# SCNano-Main.net
KiCad netlist of a schematic drawn in Altium Designer
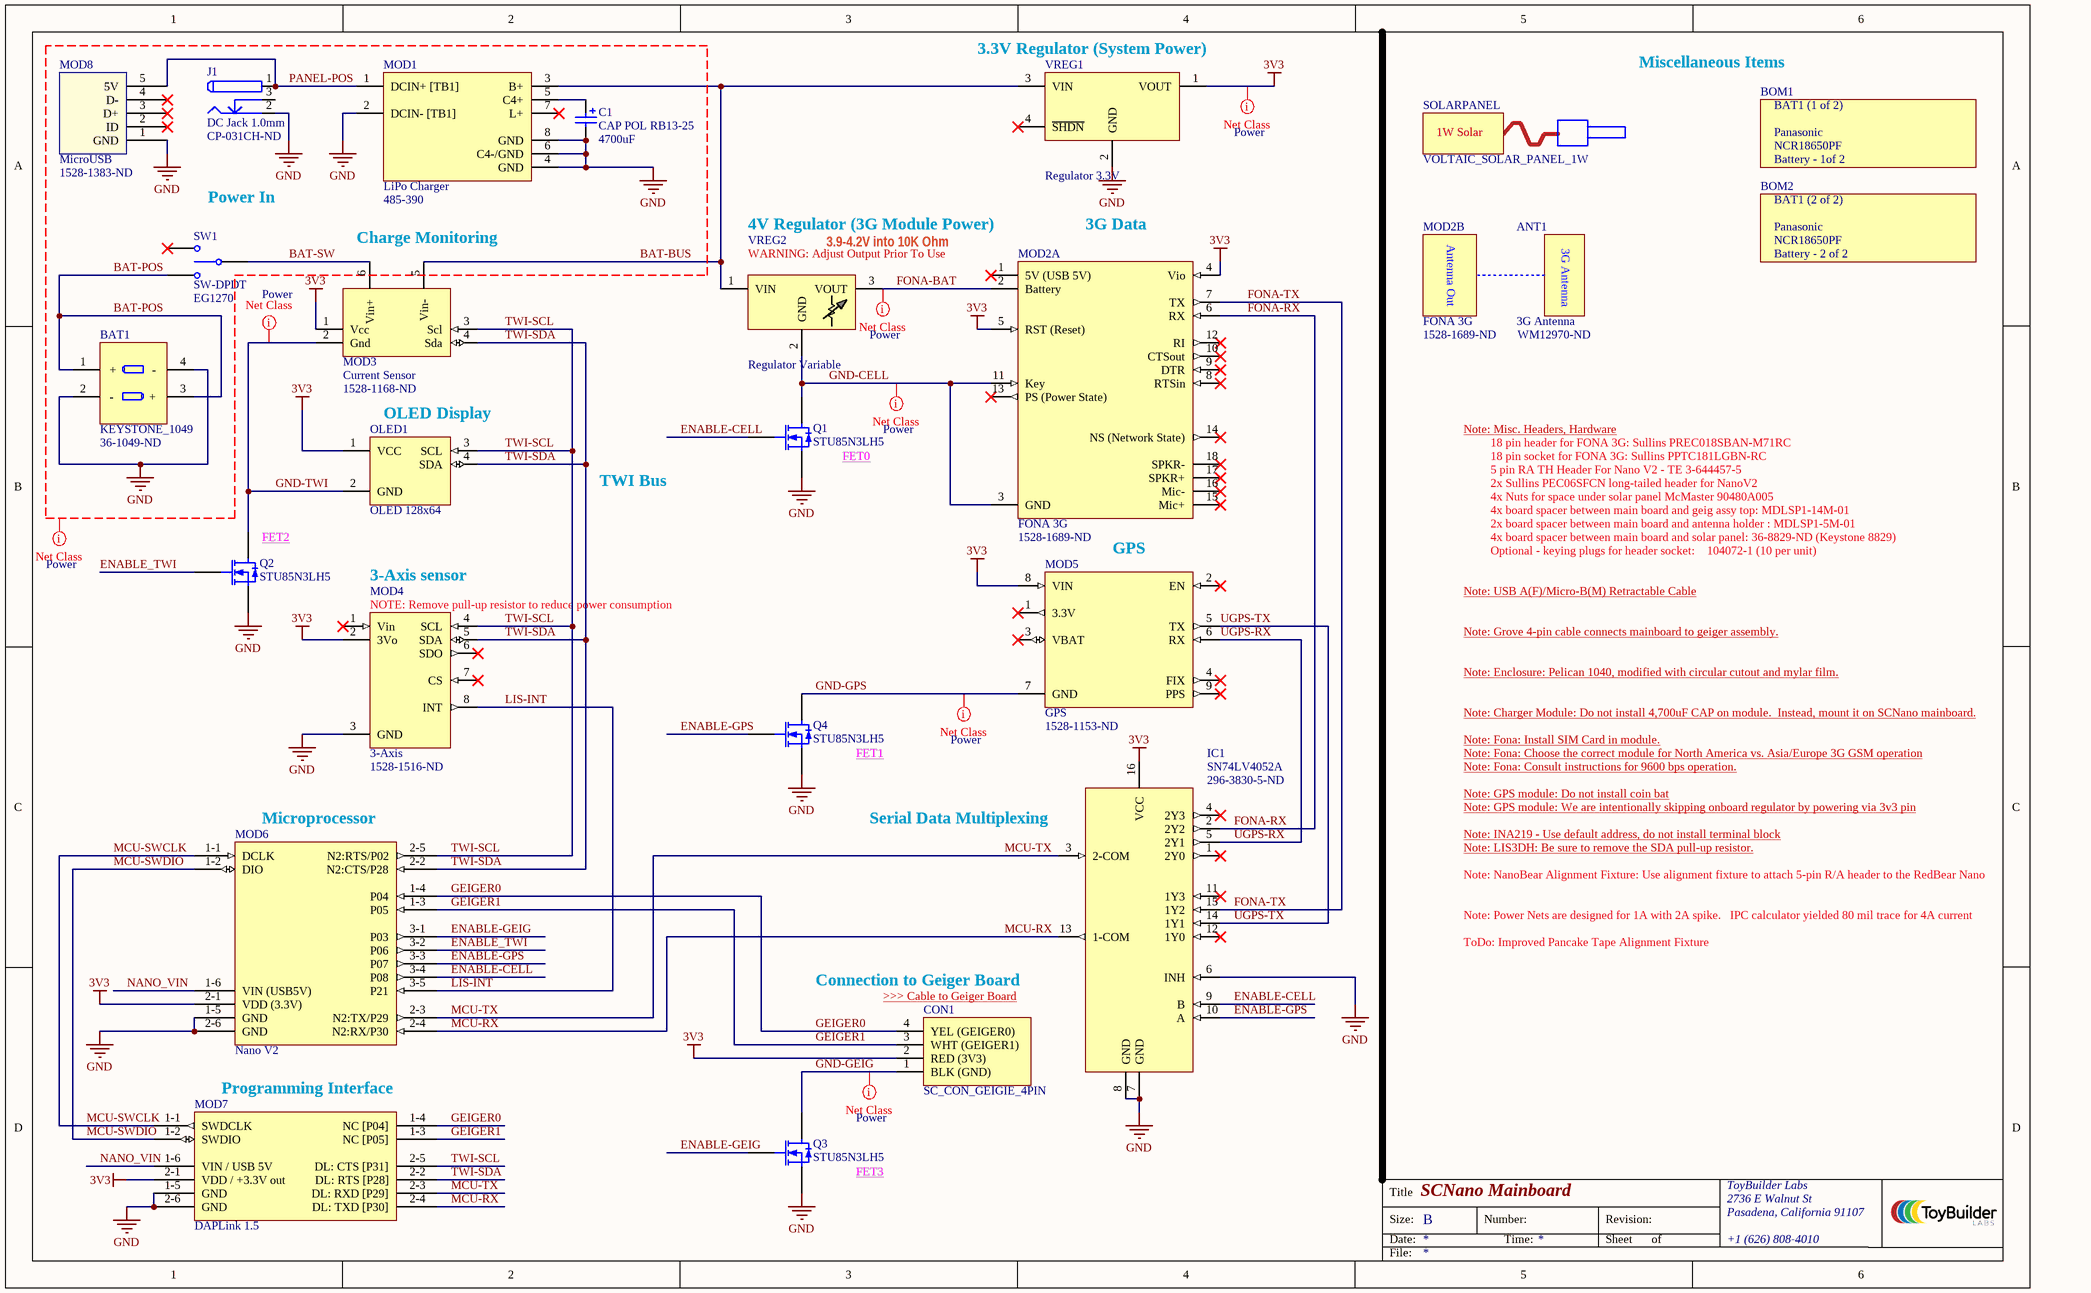
[diagram p0: SCNano-Main.SchDoc]

(export (version "E")
  (design (tool "Eeschema 10.0.6"))
  (components
    (comp (ref "ANT1")
      (value "3G Antenna")
      (footprint "MOLEX_146185-0100")
      (description "Antenna, Cellular Radio, 3G")
      (fields
        (field (name "MANUFACTURER") "Molex, LLC")
        (field (name "MANUFACTURER PART NUMBER") "1461850100")
        (field (name "SUPPLIER PART NUMBER 1") "WM12970-ND")
      )
      (libsource (lib "scnano-lib") (part "MOLEX_146185-0100"))
    )
    (comp (ref "BAT1")
      (value "KEYSTONE_1049")
      (footprint "Keystone 1049_R1")
      (description "Battery Holder, 2x18650, T/H")
      (fields
        (field (name "MANUFACTURER") "Keystone Electronics")
        (field (name "MANUFACTURER PART NUMBER") "1049")
        (field (name "SUPPLIER PART NUMBER 1") "36-1049-ND")
      )
      (libsource (lib "scnano-lib") (part "KEYSTONE_1049"))
    )
    (comp (ref "BOM1")
      (value "Battery - 1of 2")
      (footprint "BAT18650")
      (description "Additional BOM Item")
      (fields
        (field (name "MANUFACTURER") "Panasonic")
        (field (name "MANUFACTURER PART NUMBER") "NCR18650PF")
        (field (name "LOCATION") "BAT1 (1 of 2)")
      )
      (libsource (lib "TBL Common") (part "BOM Entry"))
    )
    (comp (ref "BOM2")
      (value "Battery - 2 of 2")
      (footprint "BAT18650")
      (description "Additional BOM Item")
      (fields
        (field (name "MANUFACTURER") "Panasonic")
        (field (name "MANUFACTURER PART NUMBER") "NCR18650PF")
        (field (name "LOCATION") "BAT1 (2 of 2)")
      )
      (libsource (lib "TBL Common") (part "BOM Entry"))
    )
    (comp (ref "C1")
      (value "CAP POL RB13-25")
      (footprint "RB13-25")
      (description "Polarized Capacitor (Radial)")
      (fields (field (name "ALTIUM_VALUE") "4700uF") (field (name "PUBLISHER") "Altium Limited"))
      (libsource (lib "scnano-lib") (part "CAP POL RB13-25"))
    )
    (comp (ref "CON1")
      (value "SC_CON_GEIGIE_4PIN")
      (footprint "NSTECH 1125S")
      (description "Grove 4 Pin Connector Female T/H, labeled for Safecast Geiegie products")
      (fields
        (field (name "MANUFACTURER") "Grove")
        (field (name "MANUFACTURER PART NUMBER") "4 Pin Connector")
      )
      (libsource (lib "scnano-lib") (part "SC_CON_GEIGIE_4PIN"))
    )
    (comp (ref "IC1")
      (value "SN74LV4052A")
      (footprint "N0016A")
      (description "Dual 4-Channel Analog Multiplexer/Demultiplexer DIP-16")
      (fields
        (field (name "MANUFACTURER") "Texas Instruments")
        (field (name "MANUFACTURER PART NUMBER") "SN74LV4052AN")
        (field (name "SUPPLIER PART NUMBER 1") "296-3830-5-ND")
      )
      (libsource (lib "scnano-lib") (part "SN74LV4052A"))
    )
    (comp (ref "J1")
      (value "DC Jack 1.0mm")
      (footprint "CUI_PJ-031CH")
      (description "DC Jack, 1.0 x 3.4 mm (for 1.1 x 3.5 mm plug). T/H")
      (fields
        (field (name "MANUFACTURER") "CUI Inc.")
        (field (name "MANUFACTURER PART NUMBER") "PJ-031CH")
        (field (name "SUPPLIER PART NUMBER 1") "CP-031CH-ND")
        (field (name "PUBLISHER") "Altium Limited")
      )
      (libsource (lib "scnano-lib") (part "CUI_PJ-031CH"))
    )
    (comp (ref "MOD1")
      (value "LiPo Charger")
      (footprint "ADAFRUIT 390")
      (description "Adafruit DC / Solar Lithium Ion/Polymer charger - v2")
      (fields
        (field (name "MANUFACTURER") "Adafruit Industries LLC")
        (field (name "MANUFACTURER PART NUMBER") "390")
        (field (name "SUPPLIER PART NUMBER 1") "485-390")
      )
      (libsource (lib "scnano-lib") (part "ADAFRUIT_390"))
    )
    (comp (ref "MOD2")
      (value "FONA 3G")
      (footprint "ADAFRUIT 2687_RA")
      (description "Adafruit FONA 3G Cellular + GPS Breakout")
      (fields
        (field (name "MANUFACTURER") "Adafruit Industries LLC")
        (field (name "MANUFACTURER PART NUMBER") "2687")
        (field (name "SUPPLIER PART NUMBER 1") "1528-1689-ND")
      )
      (libsource (lib "scnano-lib") (part "ADAFRUIT_2687_2691"))
    )
    (comp (ref "MOD3")
      (value "Current Sensor")
      (footprint "ADAFRUIT 904")
      (description "Adafruit INA219 High Side DC Current Sensor Breakout")
      (fields
        (field (name "MANUFACTURER") "Adafruit Industries LLC")
        (field (name "MANUFACTURER PART NUMBER") "904")
        (field (name "SUPPLIER PART NUMBER 1") "1528-1168-ND")
      )
      (libsource (lib "scnano-lib") (part "ADAFRUIT_904"))
    )
    (comp (ref "MOD4")
      (value "3-Axis")
      (footprint "ADAFRUIT_2809")
      (description "Adafruit high-resolution ultra low-power triaxial (3-axis) accelerometer module (LIS3DH)")
      (fields
        (field (name "MANUFACTURER") "Adafruit Industries LLC")
        (field (name "MANUFACTURER PART NUMBER") "2809")
        (field (name "SUPPLIER PART NUMBER 1") "1528-1516-ND")
      )
      (libsource (lib "scnano-lib") (part "ADAFRUIT_2809"))
    )
    (comp (ref "MOD5")
      (value "GPS")
      (footprint "ADAFRUIT 746")
      (description "Adafruit Ultimate GPS Breakout - 66 channel w/10 Hz updates - Version 3")
      (fields
        (field (name "MANUFACTURER") "Adafruit Industries LLC")
        (field (name "MANUFACTURER PART NUMBER") "746")
        (field (name "SUPPLIER PART NUMBER 1") "1528-1153-ND")
      )
      (libsource (lib "scnano-lib") (part "ADAFRUIT_746"))
    )
    (comp (ref "MOD6")
      (value "Nano V2")
      (footprint "REDBEAR NANO V2")
      (description "Redbear Nano V2 Plus - nRF52832 processor module")
      (fields
        (field (name "MANUFACTURER") "RedBear")
        (field (name "MANUFACTURER PART NUMBER") "Nano V2 Plus")
      )
      (libsource (lib "scnano-lib") (part "REDBEAR_NANO_V2PLUS"))
    )
    (comp (ref "MOD7")
      (value "DAPLink 1.5")
      (footprint "REDBEAR DAPLINK 1.5")
      (description "Redbear DAPLink 1.5 (included in purchase with BLE Nano)")
      (fields (field (name "MANUFACTURER") "RedBear") (field (name "MANUFACTURER PART NUMBER") "Daplink 1.5"))
      (libsource (lib "scnano-lib") (part "REDBEAR_DAPLINK_1_5"))
    )
    (comp (ref "MOD8")
      (value "MicroUSB")
      (footprint "ADAFRUIT_1833")
      (description "Adafruit 1833 MicroUSB Breakout Module")
      (fields
        (field (name "MANUFACTURER") "Adafruit Industries LLC")
        (field (name "MANUFACTURER PART NUMBER") "1833")
        (field (name "SUPPLIER PART NUMBER 1") "1528-1383-ND")
      )
      (libsource (lib "scnano-lib") (part "ADAFRUIT_1833"))
    )
    (comp (ref "OLED1")
      (value "OLED 128x64")
      (footprint "IIC_OLED_960")
      (description "IIC 0.96\" Inches White I2C 128x64 OLED LCD Display Module, with VCC on pin 1")
      (fields (field (name "MANUFACTURER") "Acrobotic") (field (name "MANUFACTURER PART NUMBER") "DIS-00003"))
      (libsource (lib "scnano-lib") (part "IIC_OLED_960"))
    )
    (comp (ref "Q1")
      (value "STU85N3LH5")
      (footprint "TO-251-3")
      (fields
        (field (name "MANUFACTURER") "STMicroelectronics")
        (field (name "MANUFACTURER PART NUMBER") "STU85N3LHS")
      )
      (libsource (lib "scnano-lib") (part "STU85N3LH5"))
    )
    (comp (ref "Q2")
      (value "STU85N3LH5")
      (footprint "TO-251-3")
      (fields
        (field (name "MANUFACTURER") "STMicroelectronics")
        (field (name "MANUFACTURER PART NUMBER") "STU85N3LHS")
      )
      (libsource (lib "scnano-lib") (part "STU85N3LH5"))
    )
    (comp (ref "Q3")
      (value "STU85N3LH5")
      (footprint "TO-251-3")
      (fields
        (field (name "MANUFACTURER") "STMicroelectronics")
        (field (name "MANUFACTURER PART NUMBER") "STU85N3LHS")
      )
      (libsource (lib "scnano-lib") (part "STU85N3LH5"))
    )
    (comp (ref "Q4")
      (value "STU85N3LH5")
      (footprint "TO-251-3")
      (fields
        (field (name "MANUFACTURER") "STMicroelectronics")
        (field (name "MANUFACTURER PART NUMBER") "STU85N3LHS")
      )
      (libsource (lib "scnano-lib") (part "STU85N3LH5"))
    )
    (comp (ref "SOLARPANEL")
      (value "VOLTAIC_SOLAR_PANEL_1W")
      (footprint "VOLTAIC_SOLAR_PANEL_1W")
      (description "1 Watt Solar Panel")
      (fields (field (name "MANUFACTURER") "Voltaic"))
      (libsource (lib "scnano-lib") (part "VOLTAIC_SOLAR_PANEL_1W"))
    )
    (comp (ref "SW1")
      (value "SW-DPDT")
      (footprint "E-SWITCH EG1270")
      (description "SWITCH SLIDE DPDT 200MA 30V")
      (fields
        (field (name "MANUFACTURER") "E-Switch")
        (field (name "MANUFACTURER PART NUMBER") "EG1270")
        (field (name "SUPPLIER PART NUMBER 1") "EG1270")
      )
      (libsource (lib "scnano-lib") (part "EG1270"))
    )
    (comp (ref "VREG1")
      (value "Regulator 3.3V")
      (footprint "POLOLU_2122")
      (description "Pololu 3.3V Step-Up/Step-Down Voltage Regulator Module (S7V8F3)")
      (fields (field (name "MANUFACTURER") "Pololou") (field (name "MANUFACTURER PART NUMBER") "2122"))
      (libsource (lib "scnano-lib") (part "POLOLU_2122"))
    )
    (comp (ref "VREG2")
      (value "Regulator Variable")
      (footprint "POLOLU_791")
      (description "Pololu Adjustable Boost Regulator Module (2.5-9.5V)")
      (fields (field (name "MANUFACTURER") "Pololou") (field (name "MANUFACTURER PART NUMBER") "791"))
      (libsource (lib "scnano-lib") (part "POLULU_791"))
    )
  )
  (nets
    (net (code "1") (name "/BAT-BUS") (class "Default")
      (node (ref "MOD1") (pin "3") (pinfunction "B+_3") (pintype "passive"))
      (node (ref "MOD3") (pin "5") (pinfunction "Vin-_5") (pintype "passive"))
      (node (ref "VREG1") (pin "3") (pinfunction "VIN_3") (pintype "passive"))
      (node (ref "VREG2") (pin "1") (pinfunction "VIN_1") (pintype "passive"))
    )
    (net (code "2") (name "/BAT-POS") (class "Default")
      (node (ref "BAT1") (pin "1") (pinfunction "+_1") (pintype "passive"))
      (node (ref "BAT1") (pin "3") (pinfunction "+_3") (pintype "passive"))
      (node (ref "SW1") (pin "1") (pinfunction "1_1") (pintype "passive"))
    )
    (net (code "3") (name "/BAT-SW") (class "Default")
      (node (ref "MOD3") (pin "6") (pinfunction "Vin+_6") (pintype "passive"))
      (node (ref "SW1") (pin "2") (pinfunction "2_2") (pintype "passive"))
    )
    (net (code "4") (name "/ENABLE-CELL") (class "Default")
      (node (ref "IC1") (pin "9") (pinfunction "B_9") (pintype "input"))
      (node (ref "MOD6") (pin "3-4") (pinfunction "P08_3-4") (pintype "output"))
      (node (ref "Q1") (pin "1") (pinfunction "G_1") (pintype "passive"))
    )
    (net (code "5") (name "/ENABLE-GEIG") (class "Default")
      (node (ref "MOD6") (pin "3-1") (pinfunction "P03_3-1") (pintype "output"))
      (node (ref "Q3") (pin "1") (pinfunction "G_1") (pintype "passive"))
    )
    (net (code "6") (name "/ENABLE-GPS") (class "Default")
      (node (ref "IC1") (pin "10") (pinfunction "A_10") (pintype "input"))
      (node (ref "MOD6") (pin "3-3") (pinfunction "P07_3-3") (pintype "output"))
      (node (ref "Q4") (pin "1") (pinfunction "G_1") (pintype "passive"))
    )
    (net (code "7") (name "/ENABLE_TWI") (class "Default")
      (node (ref "MOD6") (pin "3-2") (pinfunction "P06_3-2") (pintype "output"))
      (node (ref "Q2") (pin "1") (pinfunction "G_1") (pintype "passive"))
    )
    (net (code "8") (name "/FONA-BAT") (class "Default")
      (node (ref "MOD2") (pin "2") (pinfunction "Battery_2") (pintype "passive"))
      (node (ref "VREG2") (pin "3") (pinfunction "VOUT_3") (pintype "passive"))
    )
    (net (code "9") (name "/FONA-RX") (class "Default")
      (node (ref "IC1") (pin "2") (pinfunction "2Y2_2") (pintype "output"))
      (node (ref "MOD2") (pin "6") (pinfunction "RX_6") (pintype "input"))
    )
    (net (code "10") (name "/FONA-TX") (class "Default")
      (node (ref "IC1") (pin "15") (pinfunction "1Y2_15") (pintype "input"))
      (node (ref "MOD2") (pin "7") (pinfunction "TX_7") (pintype "output"))
    )
    (net (code "11") (name "/GEIGER0") (class "Default")
      (node (ref "CON1") (pin "4") (pinfunction "YEL_(GEIGER0)_4") (pintype "passive"))
      (node (ref "MOD6") (pin "1-4") (pinfunction "P04_1-4") (pintype "input"))
      (node (ref "MOD7") (pin "1-4") (pinfunction "NC_[P04]_1-4") (pintype "passive"))
    )
    (net (code "12") (name "/GEIGER1") (class "Default")
      (node (ref "CON1") (pin "3") (pinfunction "WHT_(GEIGER1)_3") (pintype "passive"))
      (node (ref "MOD6") (pin "1-3") (pinfunction "P05_1-3") (pintype "input"))
      (node (ref "MOD7") (pin "1-3") (pinfunction "NC_[P05]_1-3") (pintype "passive"))
    )
    (net (code "13") (name "/GND-CELL") (class "Default")
      (node (ref "MOD2") (pin "11") (pinfunction "Key_11") (pintype "input"))
      (node (ref "MOD2") (pin "3") (pinfunction "GND_3") (pintype "passive"))
      (node (ref "Q1") (pin "2") (pinfunction "D_2") (pintype "passive"))
      (node (ref "VREG2") (pin "2") (pinfunction "GND_2") (pintype "passive"))
    )
    (net (code "14") (name "/GND-GEIG") (class "Default")
      (node (ref "CON1") (pin "1") (pinfunction "BLK_(GND)_1") (pintype "passive"))
      (node (ref "Q3") (pin "2") (pinfunction "D_2") (pintype "passive"))
    )
    (net (code "15") (name "/GND-GPS") (class "Default")
      (node (ref "MOD5") (pin "7") (pinfunction "GND_7") (pintype "passive"))
      (node (ref "Q4") (pin "2") (pinfunction "D_2") (pintype "passive"))
    )
    (net (code "16") (name "/GND-TWI") (class "Default")
      (node (ref "MOD3") (pin "2") (pinfunction "Gnd_2") (pintype "passive"))
      (node (ref "OLED1") (pin "2") (pinfunction "GND_2") (pintype "passive"))
      (node (ref "Q2") (pin "2") (pinfunction "D_2") (pintype "passive"))
    )
    (net (code "17") (name "/LIS-INT") (class "Default")
      (node (ref "MOD4") (pin "8") (pinfunction "INT_8") (pintype "output"))
      (node (ref "MOD6") (pin "3-5") (pinfunction "P21_3-5") (pintype "input"))
    )
    (net (code "18") (name "/MCU-RX") (class "Default")
      (node (ref "IC1") (pin "13") (pinfunction "1-COM_13") (pintype "output"))
      (node (ref "MOD6") (pin "2-4") (pinfunction "N2:RX/P30_2-4") (pintype "input"))
      (node (ref "MOD7") (pin "2-4") (pinfunction "DL:_TXD_[P30]_2-4") (pintype "passive"))
    )
    (net (code "19") (name "/MCU-SWCLK") (class "Default")
      (node (ref "MOD6") (pin "1-1") (pinfunction "DCLK_1-1") (pintype "input"))
      (node (ref "MOD7") (pin "1-1") (pinfunction "SWDCLK_1-1") (pintype "output"))
    )
    (net (code "20") (name "/MCU-SWDIO") (class "Default")
      (node (ref "MOD6") (pin "1-2") (pinfunction "DIO_1-2") (pintype "bidirectional"))
      (node (ref "MOD7") (pin "1-2") (pinfunction "SWDIO_1-2") (pintype "bidirectional"))
    )
    (net (code "21") (name "/MCU-TX") (class "Default")
      (node (ref "IC1") (pin "3") (pinfunction "2-COM_3") (pintype "input"))
      (node (ref "MOD6") (pin "2-3") (pinfunction "N2:TX/P29_2-3") (pintype "output"))
      (node (ref "MOD7") (pin "2-3") (pinfunction "DL:_RXD_[P29]_2-3") (pintype "passive"))
    )
    (net (code "22") (name "/NANO_VIN") (class "Default")
      (node (ref "MOD6") (pin "1-6") (pinfunction "VIN_(USB5V)_1-6") (pintype "passive"))
      (node (ref "MOD7") (pin "1-6") (pinfunction "VIN_/_USB_5V_1-6") (pintype "passive"))
    )
    (net (code "23") (name "/PANEL-POS") (class "Default")
      (node (ref "J1") (pin "1") (pinfunction "1_1") (pintype "power_in"))
      (node (ref "MOD1") (pin "1") (pinfunction "DCIN+_[TB1]_1") (pintype "passive"))
      (node (ref "MOD8") (pin "5") (pinfunction "5V_5") (pintype "power_in"))
    )
    (net (code "24") (name "/TWI-SCL") (class "Default")
      (node (ref "MOD3") (pin "3") (pinfunction "Scl_3") (pintype "input"))
      (node (ref "MOD4") (pin "4") (pinfunction "SCL_4") (pintype "input"))
      (node (ref "MOD6") (pin "2-5") (pinfunction "N2:RTS/P02_2-5") (pintype "output"))
      (node (ref "MOD7") (pin "2-5") (pinfunction "DL:_CTS_[P31]_2-5") (pintype "passive"))
      (node (ref "OLED1") (pin "3") (pinfunction "SCL_3") (pintype "input"))
    )
    (net (code "25") (name "/TWI-SDA") (class "Default")
      (node (ref "MOD3") (pin "4") (pinfunction "Sda_4") (pintype "bidirectional"))
      (node (ref "MOD4") (pin "5") (pinfunction "SDA_5") (pintype "bidirectional"))
      (node (ref "MOD6") (pin "2-2") (pinfunction "N2:CTS/P28_2-2") (pintype "input"))
      (node (ref "MOD7") (pin "2-2") (pinfunction "DL:_RTS_[P28]_2-2") (pintype "passive"))
      (node (ref "OLED1") (pin "4") (pinfunction "SDA_4") (pintype "bidirectional"))
    )
    (net (code "26") (name "/UGPS-RX") (class "Default")
      (node (ref "IC1") (pin "5") (pinfunction "2Y1_5") (pintype "output"))
      (node (ref "MOD5") (pin "6") (pinfunction "RX_6") (pintype "input"))
    )
    (net (code "27") (name "/UGPS-TX") (class "Default")
      (node (ref "IC1") (pin "14") (pinfunction "1Y1_14") (pintype "input"))
      (node (ref "MOD5") (pin "5") (pinfunction "TX_5") (pintype "output"))
    )
    (net (code "28") (name "3V3") (class "Default")
      (node (ref "CON1") (pin "2") (pinfunction "RED_(3V3)_2") (pintype "passive"))
      (node (ref "IC1") (pin "16") (pinfunction "VCC_16") (pintype "passive"))
      (node (ref "MOD2") (pin "4") (pinfunction "Vio_4") (pintype "input"))
      (node (ref "MOD2") (pin "5") (pinfunction "RST_(Reset)_5") (pintype "input"))
      (node (ref "MOD3") (pin "1") (pinfunction "Vcc_1") (pintype "passive"))
      (node (ref "MOD4") (pin "2") (pinfunction "3Vo_2") (pintype "power_in"))
      (node (ref "MOD5") (pin "8") (pinfunction "VIN_8") (pintype "input"))
      (node (ref "MOD6") (pin "2-1") (pinfunction "VDD_(3.3V)_2-1") (pintype "passive"))
      (node (ref "MOD7") (pin "2-1") (pinfunction "VDD_/_+3.3V_out_2-1") (pintype "passive"))
      (node (ref "OLED1") (pin "1") (pinfunction "VCC_1") (pintype "passive"))
      (node (ref "VREG1") (pin "1") (pinfunction "VOUT_1") (pintype "power_in"))
    )
    (net (code "29") (name "GND") (class "Default")
      (node (ref "BAT1") (pin "2") (pinfunction "-_2") (pintype "passive"))
      (node (ref "BAT1") (pin "4") (pinfunction "-_4") (pintype "passive"))
      (node (ref "C1") (pin "2") (pinfunction "2_2") (pintype "passive"))
      (node (ref "IC1") (pin "6") (pinfunction "INH_6") (pintype "input"))
      (node (ref "IC1") (pin "7") (pinfunction "GND_7") (pintype "passive"))
      (node (ref "IC1") (pin "8") (pinfunction "GND_8") (pintype "passive"))
      (node (ref "J1") (pin "2") (pinfunction "2_2") (pintype "power_in"))
      (node (ref "MOD1") (pin "2") (pinfunction "DCIN-_[TB1]_2") (pintype "passive"))
      (node (ref "MOD1") (pin "4") (pinfunction "GND_4") (pintype "passive"))
      (node (ref "MOD1") (pin "6") (pinfunction "C4-/GND_6") (pintype "power_in"))
      (node (ref "MOD1") (pin "8") (pinfunction "GND_8") (pintype "passive"))
      (node (ref "MOD4") (pin "3") (pinfunction "GND_3") (pintype "passive"))
      (node (ref "MOD6") (pin "1-5") (pinfunction "GND_1-5") (pintype "passive"))
      (node (ref "MOD6") (pin "2-6") (pinfunction "GND_2-6") (pintype "passive"))
      (node (ref "MOD7") (pin "1-5") (pinfunction "GND_1-5") (pintype "passive"))
      (node (ref "MOD7") (pin "2-6") (pinfunction "GND_2-6") (pintype "passive"))
      (node (ref "MOD8") (pin "1") (pinfunction "GND_1") (pintype "power_in"))
      (node (ref "Q1") (pin "3") (pinfunction "S_3") (pintype "passive"))
      (node (ref "Q2") (pin "3") (pinfunction "S_3") (pintype "passive"))
      (node (ref "Q3") (pin "3") (pinfunction "S_3") (pintype "passive"))
      (node (ref "Q4") (pin "3") (pinfunction "S_3") (pintype "passive"))
      (node (ref "VREG1") (pin "2") (pinfunction "GND_2") (pintype "passive"))
    )
    (net (code "30") (name "Net-(MOD1-C4+)") (class "Default")
      (node (ref "C1") (pin "1") (pinfunction "1_1") (pintype "passive"))
      (node (ref "MOD1") (pin "5") (pinfunction "C4+_5") (pintype "power_in"))
    )
    (net (code "31") (name "unconnected-(IC1-1Y0-Pad12)") (class "Default")
      (node (ref "IC1") (pin "12") (pinfunction "1Y0_12") (pintype "input+no_connect"))
    )
    (net (code "32") (name "unconnected-(IC1-1Y3-Pad11)") (class "Default")
      (node (ref "IC1") (pin "11") (pinfunction "1Y3_11") (pintype "input+no_connect"))
    )
    (net (code "33") (name "unconnected-(IC1-2Y0-Pad1)") (class "Default")
      (node (ref "IC1") (pin "1") (pinfunction "2Y0_1") (pintype "output+no_connect"))
    )
    (net (code "34") (name "unconnected-(IC1-2Y3-Pad4)") (class "Default")
      (node (ref "IC1") (pin "4") (pinfunction "2Y3_4") (pintype "output+no_connect"))
    )
    (net (code "35") (name "unconnected-(J1-Pad3)") (class "Default")
      (node (ref "J1") (pin "3") (pinfunction "3_3") (pintype "power_in"))
    )
    (net (code "36") (name "unconnected-(MOD1-L+-Pad7)") (class "Default")
      (node (ref "MOD1") (pin "7") (pinfunction "L+_7") (pintype "passive+no_connect"))
    )
    (net (code "37") (name "unconnected-(MOD2A-5V_(USB_5V)-Pad1)") (class "Default")
      (node (ref "MOD2") (pin "1") (pinfunction "5V_(USB_5V)_1") (pintype "passive+no_connect"))
    )
    (net (code "38") (name "unconnected-(MOD2A-CTSout-Pad10)") (class "Default")
      (node (ref "MOD2") (pin "10") (pinfunction "CTSout_10") (pintype "output+no_connect"))
    )
    (net (code "39") (name "unconnected-(MOD2A-DTR-Pad9)") (class "Default")
      (node (ref "MOD2") (pin "9") (pinfunction "DTR_9") (pintype "input+no_connect"))
    )
    (net (code "40") (name "unconnected-(MOD2A-Mic+-Pad15)") (class "Default")
      (node (ref "MOD2") (pin "15") (pinfunction "Mic+_15") (pintype "passive+no_connect"))
    )
    (net (code "41") (name "unconnected-(MOD2A-Mic--Pad16)") (class "Default")
      (node (ref "MOD2") (pin "16") (pinfunction "Mic-_16") (pintype "passive+no_connect"))
    )
    (net (code "42") (name "unconnected-(MOD2A-NS_(Network_State)-Pad14)") (class "Default")
      (node (ref "MOD2") (pin "14") (pinfunction "NS_(Network_State)_14") (pintype "output+no_connect"))
    )
    (net (code "43") (name "unconnected-(MOD2A-PS_(Power_State)-Pad13)") (class "Default")
      (node (ref "MOD2") (pin "13") (pinfunction "PS_(Power_State)_13") (pintype "output+no_connect"))
    )
    (net (code "44") (name "unconnected-(MOD2A-RI-Pad12)") (class "Default")
      (node (ref "MOD2") (pin "12") (pinfunction "RI_12") (pintype "output+no_connect"))
    )
    (net (code "45") (name "unconnected-(MOD2A-RTSin-Pad8)") (class "Default")
      (node (ref "MOD2") (pin "8") (pinfunction "RTSin_8") (pintype "input+no_connect"))
    )
    (net (code "46") (name "unconnected-(MOD2A-SPKR+-Pad17)") (class "Default")
      (node (ref "MOD2") (pin "17") (pinfunction "SPKR+_17") (pintype "passive+no_connect"))
    )
    (net (code "47") (name "unconnected-(MOD2A-SPKR--Pad18)") (class "Default")
      (node (ref "MOD2") (pin "18") (pinfunction "SPKR-_18") (pintype "passive+no_connect"))
    )
    (net (code "48") (name "unconnected-(MOD4-CS-Pad7)") (class "Default")
      (node (ref "MOD4") (pin "7") (pinfunction "CS_7") (pintype "input+no_connect"))
    )
    (net (code "49") (name "unconnected-(MOD4-SDO-Pad6)") (class "Default")
      (node (ref "MOD4") (pin "6") (pinfunction "SDO_6") (pintype "output+no_connect"))
    )
    (net (code "50") (name "unconnected-(MOD4-Vin-Pad1)") (class "Default")
      (node (ref "MOD4") (pin "1") (pinfunction "Vin_1") (pintype "input+no_connect"))
    )
    (net (code "51") (name "unconnected-(MOD5-3.3V-Pad1)") (class "Default")
      (node (ref "MOD5") (pin "1") (pinfunction "3.3V_1") (pintype "output+no_connect"))
    )
    (net (code "52") (name "unconnected-(MOD5-EN-Pad2)") (class "Default")
      (node (ref "MOD5") (pin "2") (pinfunction "EN_2") (pintype "input+no_connect"))
    )
    (net (code "53") (name "unconnected-(MOD5-FIX-Pad4)") (class "Default")
      (node (ref "MOD5") (pin "4") (pinfunction "FIX_4") (pintype "output+no_connect"))
    )
    (net (code "54") (name "unconnected-(MOD5-PPS-Pad9)") (class "Default")
      (node (ref "MOD5") (pin "9") (pinfunction "PPS_9") (pintype "output+no_connect"))
    )
    (net (code "55") (name "unconnected-(MOD5-VBAT-Pad3)") (class "Default")
      (node (ref "MOD5") (pin "3") (pinfunction "VBAT_3") (pintype "bidirectional+no_connect"))
    )
    (net (code "56") (name "unconnected-(MOD8-D+-Pad3)") (class "Default")
      (node (ref "MOD8") (pin "3") (pinfunction "D+_3") (pintype "power_in+no_connect"))
    )
    (net (code "57") (name "unconnected-(MOD8-D--Pad4)") (class "Default")
      (node (ref "MOD8") (pin "4") (pinfunction "D-_4") (pintype "power_in+no_connect"))
    )
    (net (code "58") (name "unconnected-(MOD8-ID-Pad2)") (class "Default")
      (node (ref "MOD8") (pin "2") (pinfunction "ID_2") (pintype "power_in+no_connect"))
    )
    (net (code "59") (name "unconnected-(SW1-Pad3)") (class "Default")
      (node (ref "SW1") (pin "3") (pinfunction "3_3") (pintype "passive+no_connect"))
    )
    (net (code "60") (name "unconnected-(VREG1-~{SHDN}-Pad4)") (class "Default")
      (node (ref "VREG1") (pin "4") (pinfunction "~{SHDN}_4") (pintype "passive+no_connect"))
    )
  )
)
